# pi.net
KiCad netlist of a schematic drawn in EAGLE
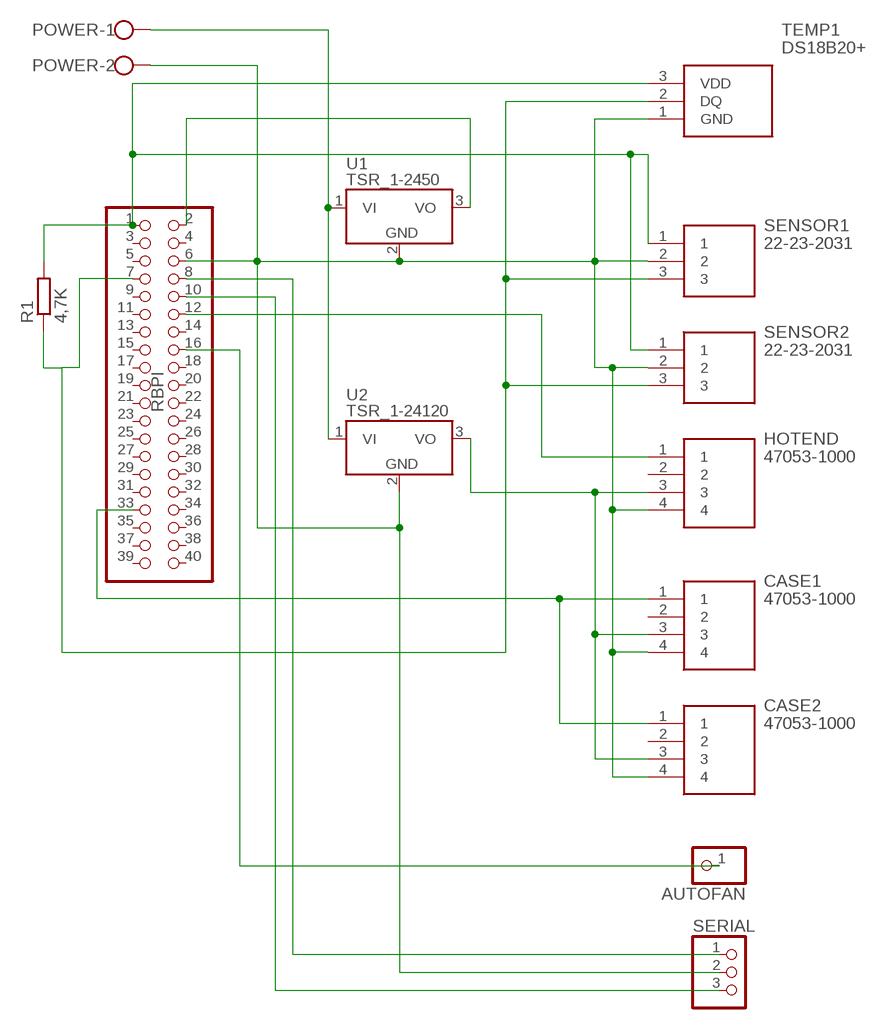
[diagram p0: schematic, sheet 1]

(export (version "E")
  (design (tool "Eeschema 10.0.6"))
  (components
    (comp (ref "AUTOFAN")
      (value "PINHD-1X1")
      (footprint "eagle-import:1X01")
      (libsource (lib "eagle-import") (part "PINHD-1X1"))
    )
    (comp (ref "CASE1")
      (value "47053-1000")
      (footprint "eagle-import:47053-1000")
      (fields (field (name "MOUSER_PART_NUMBER") "538-47053-1000"))
      (libsource (lib "eagle-import") (part "47053-1000"))
    )
    (comp (ref "CASE2")
      (value "47053-1000")
      (footprint "eagle-import:47053-1000")
      (fields (field (name "MOUSER_PART_NUMBER") "538-47053-1000"))
      (libsource (lib "eagle-import") (part "47053-1000"))
    )
    (comp (ref "HOTEND")
      (value "47053-1000")
      (footprint "eagle-import:47053-1000")
      (fields (field (name "MOUSER_PART_NUMBER") "538-47053-1000"))
      (libsource (lib "eagle-import") (part "47053-1000"))
    )
    (comp (ref "POWER")
      (value "W237-102")
      (footprint "eagle-import:W237-102")
      (fields (field (name "MPN") "237-102"))
      (libsource (lib "eagle-import") (part "W237-102"))
    )
    (comp (ref "R1")
      (value "4,7K")
      (footprint "eagle-import:0411_12")
      (libsource (lib "eagle-import") (part "R-EU_0411/12"))
    )
    (comp (ref "RBPI")
      (value "PINHD-2X20")
      (footprint "eagle-import:2X20")
      (libsource (lib "eagle-import") (part "PINHD-2X20"))
    )
    (comp (ref "SENSOR1")
      (value "22-23-2031")
      (footprint "eagle-import:SHDR3W87P0X254_1X3_747X635X843")
      (fields (field (name "MOUSER_PART_NUMBER") "538-22-23-2031"))
      (libsource (lib "eagle-import") (part "22-23-2031"))
    )
    (comp (ref "SENSOR2")
      (value "22-23-2031")
      (footprint "eagle-import:SHDR3W87P0X254_1X3_747X635X843")
      (fields (field (name "MOUSER_PART_NUMBER") "538-22-23-2031"))
      (libsource (lib "eagle-import") (part "22-23-2031"))
    )
    (comp (ref "SERIAL")
      (value "PINHD-1X3")
      (footprint "eagle-import:1X03")
      (libsource (lib "eagle-import") (part "PINHD-1X3"))
    )
    (comp (ref "TEMP1")
      (value "DS18B20+")
      (footprint "eagle-import:TO-92")
      (fields (field (name "MOUSER_PART_NUMBER") "700-DS18B20+"))
      (libsource (lib "eagle-import") (part "DS18B20+"))
    )
    (comp (ref "U1")
      (value "TSR_1-2450")
      (footprint "eagle-import:TSR-1")
      (libsource (lib "eagle-import") (part "TSR_1-2450"))
    )
    (comp (ref "U2")
      (value "TSR_1-24120")
      (footprint "eagle-import:TSR-1")
      (libsource (lib "eagle-import") (part "TSR_1-24120"))
    )
  )
  (nets
    (net (code "1") (name "Net-(AUTOFAN-Pad1)") (class "Default")
      (node (ref "AUTOFAN") (pin "1") (pinfunction "1_1") (pintype "passive"))
      (node (ref "RBPI") (pin "16") (pinfunction "16_16") (pintype "passive"))
    )
    (net (code "2") (name "Net-(CASE1-Pad1)") (class "Default")
      (node (ref "CASE1") (pin "1") (pinfunction "1_1") (pintype "bidirectional"))
      (node (ref "CASE2") (pin "1") (pinfunction "1_1") (pintype "bidirectional"))
      (node (ref "RBPI") (pin "33") (pinfunction "33_33") (pintype "passive"))
    )
    (net (code "3") (name "Net-(HOTEND-Pad1)") (class "Default")
      (node (ref "HOTEND") (pin "1") (pinfunction "1_1") (pintype "bidirectional"))
      (node (ref "RBPI") (pin "12") (pinfunction "12_12") (pintype "passive"))
    )
    (net (code "4") (name "Net-(POWERA-KL)") (class "Default")
      (node (ref "POWER") (pin "1") (pinfunction "KL_1") (pintype "passive"))
      (node (ref "U1") (pin "1") (pinfunction "VI_1") (pintype "power_in"))
      (node (ref "U2") (pin "1") (pinfunction "VI_1") (pintype "power_in"))
    )
    (net (code "5") (name "Net-(POWERB-KL)") (class "Default")
      (node (ref "CASE1") (pin "4") (pinfunction "4_4") (pintype "bidirectional"))
      (node (ref "CASE2") (pin "4") (pinfunction "4_4") (pintype "bidirectional"))
      (node (ref "HOTEND") (pin "4") (pinfunction "4_4") (pintype "bidirectional"))
      (node (ref "POWER") (pin "2") (pinfunction "KL_2") (pintype "passive"))
      (node (ref "RBPI") (pin "6") (pinfunction "6_6") (pintype "passive"))
      (node (ref "SENSOR1") (pin "2") (pinfunction "2_2") (pintype "bidirectional"))
      (node (ref "SENSOR2") (pin "2") (pinfunction "2_2") (pintype "bidirectional"))
      (node (ref "SERIAL") (pin "2") (pinfunction "2_2") (pintype "passive"))
      (node (ref "TEMP1") (pin "1") (pinfunction "GND_1") (pintype "power_in"))
      (node (ref "U1") (pin "2") (pinfunction "GND_2") (pintype "power_in"))
      (node (ref "U2") (pin "2") (pinfunction "GND_2") (pintype "power_in"))
    )
    (net (code "6") (name "Net-(RBPI-Pad8)") (class "Default")
      (node (ref "RBPI") (pin "8") (pinfunction "8_8") (pintype "passive"))
      (node (ref "SERIAL") (pin "1") (pinfunction "1_1") (pintype "passive"))
    )
    (net (code "7") (name "Net-(RBPI-Pad10)") (class "Default")
      (node (ref "RBPI") (pin "10") (pinfunction "10_10") (pintype "passive"))
      (node (ref "SERIAL") (pin "3") (pinfunction "3_3") (pintype "passive"))
    )
    (net (code "8") (name "Net-(TEMP1-DQ)") (class "Default")
      (node (ref "R1") (pin "1") (pinfunction "1_1") (pintype "passive"))
      (node (ref "RBPI") (pin "7") (pinfunction "7_7") (pintype "passive"))
      (node (ref "SENSOR1") (pin "3") (pinfunction "3_3") (pintype "bidirectional"))
      (node (ref "SENSOR2") (pin "3") (pinfunction "3_3") (pintype "bidirectional"))
      (node (ref "TEMP1") (pin "2") (pinfunction "DQ_2") (pintype "bidirectional"))
    )
    (net (code "9") (name "Net-(TEMP1-VDD)") (class "Default")
      (node (ref "R1") (pin "2") (pinfunction "2_2") (pintype "passive"))
      (node (ref "RBPI") (pin "1") (pinfunction "1_1") (pintype "passive"))
      (node (ref "SENSOR1") (pin "1") (pinfunction "1_1") (pintype "bidirectional"))
      (node (ref "SENSOR2") (pin "1") (pinfunction "1_1") (pintype "bidirectional"))
      (node (ref "TEMP1") (pin "3") (pinfunction "VDD_3") (pintype "power_in"))
    )
    (net (code "10") (name "Net-(U1-VO)") (class "Default")
      (node (ref "RBPI") (pin "2") (pinfunction "2_2") (pintype "passive"))
      (node (ref "U1") (pin "3") (pinfunction "VO_3") (pintype "power_in"))
    )
    (net (code "11") (name "Net-(U2-VO)") (class "Default")
      (node (ref "CASE1") (pin "3") (pinfunction "3_3") (pintype "bidirectional"))
      (node (ref "CASE2") (pin "3") (pinfunction "3_3") (pintype "bidirectional"))
      (node (ref "HOTEND") (pin "3") (pinfunction "3_3") (pintype "bidirectional"))
      (node (ref "U2") (pin "3") (pinfunction "VO_3") (pintype "power_in"))
    )
    (net (code "12") (name "unconnected-(CASE1-Pad2)") (class "Default")
      (node (ref "CASE1") (pin "2") (pinfunction "2_2") (pintype "bidirectional"))
    )
    (net (code "13") (name "unconnected-(CASE2-Pad2)") (class "Default")
      (node (ref "CASE2") (pin "2") (pinfunction "2_2") (pintype "bidirectional"))
    )
    (net (code "14") (name "unconnected-(HOTEND-Pad2)") (class "Default")
      (node (ref "HOTEND") (pin "2") (pinfunction "2_2") (pintype "bidirectional"))
    )
    (net (code "15") (name "unconnected-(RBPI-Pad3)") (class "Default")
      (node (ref "RBPI") (pin "3") (pinfunction "3_3") (pintype "passive"))
    )
    (net (code "16") (name "unconnected-(RBPI-Pad4)") (class "Default")
      (node (ref "RBPI") (pin "4") (pinfunction "4_4") (pintype "passive"))
    )
    (net (code "17") (name "unconnected-(RBPI-Pad5)") (class "Default")
      (node (ref "RBPI") (pin "5") (pinfunction "5_5") (pintype "passive"))
    )
    (net (code "18") (name "unconnected-(RBPI-Pad9)") (class "Default")
      (node (ref "RBPI") (pin "9") (pinfunction "9_9") (pintype "passive"))
    )
    (net (code "19") (name "unconnected-(RBPI-Pad11)") (class "Default")
      (node (ref "RBPI") (pin "11") (pinfunction "11_11") (pintype "passive"))
    )
    (net (code "20") (name "unconnected-(RBPI-Pad13)") (class "Default")
      (node (ref "RBPI") (pin "13") (pinfunction "13_13") (pintype "passive"))
    )
    (net (code "21") (name "unconnected-(RBPI-Pad14)") (class "Default")
      (node (ref "RBPI") (pin "14") (pinfunction "14_14") (pintype "passive"))
    )
    (net (code "22") (name "unconnected-(RBPI-Pad15)") (class "Default")
      (node (ref "RBPI") (pin "15") (pinfunction "15_15") (pintype "passive"))
    )
    (net (code "23") (name "unconnected-(RBPI-Pad17)") (class "Default")
      (node (ref "RBPI") (pin "17") (pinfunction "17_17") (pintype "passive"))
    )
    (net (code "24") (name "unconnected-(RBPI-Pad18)") (class "Default")
      (node (ref "RBPI") (pin "18") (pinfunction "18_18") (pintype "passive"))
    )
    (net (code "25") (name "unconnected-(RBPI-Pad19)") (class "Default")
      (node (ref "RBPI") (pin "19") (pinfunction "19_19") (pintype "passive"))
    )
    (net (code "26") (name "unconnected-(RBPI-Pad20)") (class "Default")
      (node (ref "RBPI") (pin "20") (pinfunction "20_20") (pintype "passive"))
    )
    (net (code "27") (name "unconnected-(RBPI-Pad21)") (class "Default")
      (node (ref "RBPI") (pin "21") (pinfunction "21_21") (pintype "passive"))
    )
    (net (code "28") (name "unconnected-(RBPI-Pad22)") (class "Default")
      (node (ref "RBPI") (pin "22") (pinfunction "22_22") (pintype "passive"))
    )
    (net (code "29") (name "unconnected-(RBPI-Pad23)") (class "Default")
      (node (ref "RBPI") (pin "23") (pinfunction "23_23") (pintype "passive"))
    )
    (net (code "30") (name "unconnected-(RBPI-Pad24)") (class "Default")
      (node (ref "RBPI") (pin "24") (pinfunction "24_24") (pintype "passive"))
    )
    (net (code "31") (name "unconnected-(RBPI-Pad25)") (class "Default")
      (node (ref "RBPI") (pin "25") (pinfunction "25_25") (pintype "passive"))
    )
    (net (code "32") (name "unconnected-(RBPI-Pad26)") (class "Default")
      (node (ref "RBPI") (pin "26") (pinfunction "26_26") (pintype "passive"))
    )
    (net (code "33") (name "unconnected-(RBPI-Pad27)") (class "Default")
      (node (ref "RBPI") (pin "27") (pinfunction "27_27") (pintype "passive"))
    )
    (net (code "34") (name "unconnected-(RBPI-Pad28)") (class "Default")
      (node (ref "RBPI") (pin "28") (pinfunction "28_28") (pintype "passive"))
    )
    (net (code "35") (name "unconnected-(RBPI-Pad29)") (class "Default")
      (node (ref "RBPI") (pin "29") (pinfunction "29_29") (pintype "passive"))
    )
    (net (code "36") (name "unconnected-(RBPI-Pad30)") (class "Default")
      (node (ref "RBPI") (pin "30") (pinfunction "30_30") (pintype "passive"))
    )
    (net (code "37") (name "unconnected-(RBPI-Pad31)") (class "Default")
      (node (ref "RBPI") (pin "31") (pinfunction "31_31") (pintype "passive"))
    )
    (net (code "38") (name "unconnected-(RBPI-Pad32)") (class "Default")
      (node (ref "RBPI") (pin "32") (pinfunction "32_32") (pintype "passive"))
    )
    (net (code "39") (name "unconnected-(RBPI-Pad34)") (class "Default")
      (node (ref "RBPI") (pin "34") (pinfunction "34_34") (pintype "passive"))
    )
    (net (code "40") (name "unconnected-(RBPI-Pad35)") (class "Default")
      (node (ref "RBPI") (pin "35") (pinfunction "35_35") (pintype "passive"))
    )
    (net (code "41") (name "unconnected-(RBPI-Pad36)") (class "Default")
      (node (ref "RBPI") (pin "36") (pinfunction "36_36") (pintype "passive"))
    )
    (net (code "42") (name "unconnected-(RBPI-Pad37)") (class "Default")
      (node (ref "RBPI") (pin "37") (pinfunction "37_37") (pintype "passive"))
    )
    (net (code "43") (name "unconnected-(RBPI-Pad38)") (class "Default")
      (node (ref "RBPI") (pin "38") (pinfunction "38_38") (pintype "passive"))
    )
    (net (code "44") (name "unconnected-(RBPI-Pad39)") (class "Default")
      (node (ref "RBPI") (pin "39") (pinfunction "39_39") (pintype "passive"))
    )
    (net (code "45") (name "unconnected-(RBPI-Pad40)") (class "Default")
      (node (ref "RBPI") (pin "40") (pinfunction "40_40") (pintype "passive"))
    )
  )
)
